# converter.net
KiCad netlist of a schematic drawn in EAGLE
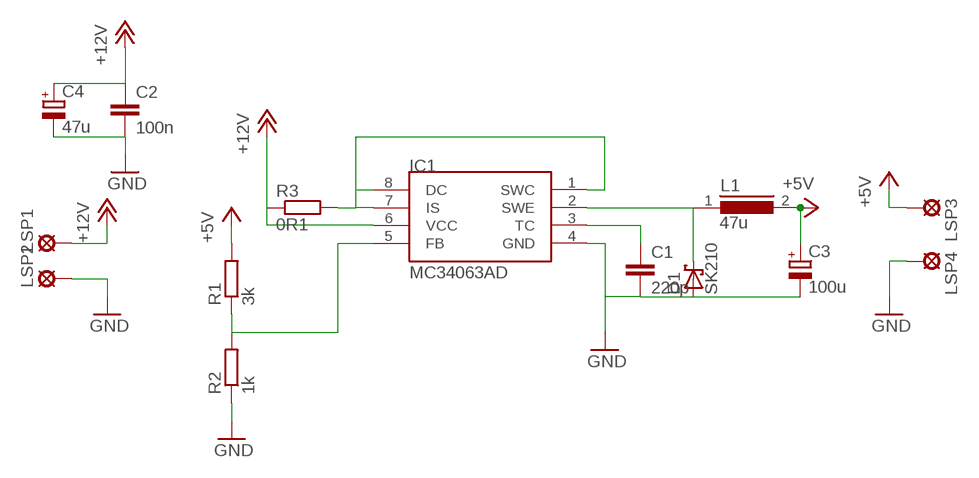
[diagram p0: schematic, sheet 1]

(export (version "E")
  (design (tool "Eeschema 10.0.6"))
  (components
    (comp (ref "C1")
      (value "220p")
      (footprint "eagle-import:C0805")
      (libsource (lib "eagle-import") (part "C-EUC0805"))
    )
    (comp (ref "C2")
      (value "100n")
      (footprint "eagle-import:C0805")
      (libsource (lib "eagle-import") (part "C-EUC0805"))
    )
    (comp (ref "C3")
      (value "100u")
      (footprint "eagle-import:PANASONIC_D")
      (libsource (lib "eagle-import") (part "CPOL-EUD"))
    )
    (comp (ref "C4")
      (value "47u")
      (footprint "eagle-import:PANASONIC_D")
      (libsource (lib "eagle-import") (part "CPOL-EUD"))
    )
    (comp (ref "D1")
      (value "SK210")
      (footprint "eagle-import:SMB")
      (libsource (lib "eagle-import") (part "SCHOTTKY-DIODESMD"))
    )
    (comp (ref "IC1")
      (value "MC34063AD")
      (footprint "eagle-import:SOIC8")
      (libsource (lib "eagle-import") (part "MC34063AD"))
    )
    (comp (ref "L1")
      (value "47u")
      (footprint "eagle-import:DR127")
      (libsource (lib "eagle-import") (part "DR127"))
    )
    (comp (ref "LSP1")
      (value "+12V")
      (footprint "eagle-import:LSP11")
      (libsource (lib "eagle-import") (part "LSP11"))
    )
    (comp (ref "LSP2")
      (value "GND")
      (footprint "eagle-import:LSP11")
      (libsource (lib "eagle-import") (part "LSP11"))
    )
    (comp (ref "LSP3")
      (value "LSP11")
      (footprint "eagle-import:LSP11")
      (libsource (lib "eagle-import") (part "LSP11"))
    )
    (comp (ref "LSP4")
      (value "LSP11")
      (footprint "eagle-import:LSP11")
      (libsource (lib "eagle-import") (part "LSP11"))
    )
    (comp (ref "R1")
      (value "3k")
      (footprint "eagle-import:R0805")
      (libsource (lib "eagle-import") (part "R-EU_R0805"))
    )
    (comp (ref "R2")
      (value "1k")
      (footprint "eagle-import:R0805")
      (libsource (lib "eagle-import") (part "R-EU_R0805"))
    )
    (comp (ref "R3")
      (value "0R1")
      (footprint "eagle-import:R0805")
      (libsource (lib "eagle-import") (part "R-EU_R0805"))
    )
  )
  (nets
    (net (code "1") (name "+5V") (class "Default")
      (node (ref "C3") (pin "+") (pinfunction "+_+") (pintype "passive"))
      (node (ref "L1") (pin "2") (pinfunction "2_2") (pintype "passive"))
      (node (ref "LSP3") (pin "MP") (pinfunction "MP_MP") (pintype "passive"))
      (node (ref "R1") (pin "2") (pinfunction "2_2") (pintype "passive"))
    )
    (net (code "2") (name "+12V") (class "Default")
      (node (ref "C2") (pin "1") (pinfunction "1_1") (pintype "passive"))
      (node (ref "C4") (pin "+") (pinfunction "+_+") (pintype "passive"))
      (node (ref "IC1") (pin "6") (pinfunction "VCC_6") (pintype "passive"))
      (node (ref "LSP1") (pin "MP") (pinfunction "MP_MP") (pintype "passive"))
      (node (ref "R3") (pin "1") (pinfunction "1_1") (pintype "passive"))
    )
    (net (code "3") (name "GND") (class "Default")
      (node (ref "C1") (pin "2") (pinfunction "2_2") (pintype "passive"))
      (node (ref "C2") (pin "2") (pinfunction "2_2") (pintype "passive"))
      (node (ref "C3") (pin "-") (pinfunction "-_-") (pintype "passive"))
      (node (ref "C4") (pin "-") (pinfunction "-_-") (pintype "passive"))
      (node (ref "D1") (pin "A") (pinfunction "A_A") (pintype "passive"))
      (node (ref "IC1") (pin "4") (pinfunction "GND_4") (pintype "passive"))
      (node (ref "LSP2") (pin "MP") (pinfunction "MP_MP") (pintype "passive"))
      (node (ref "LSP4") (pin "MP") (pinfunction "MP_MP") (pintype "passive"))
      (node (ref "R2") (pin "1") (pinfunction "1_1") (pintype "passive"))
    )
    (net (code "4") (name "Net-(IC1-DC)") (class "Default")
      (node (ref "IC1") (pin "1") (pinfunction "SWC_1") (pintype "passive"))
      (node (ref "IC1") (pin "7") (pinfunction "IS_7") (pintype "passive"))
      (node (ref "IC1") (pin "8") (pinfunction "DC_8") (pintype "passive"))
      (node (ref "R3") (pin "2") (pinfunction "2_2") (pintype "passive"))
    )
    (net (code "5") (name "Net-(IC1-FB)") (class "Default")
      (node (ref "IC1") (pin "5") (pinfunction "FB_5") (pintype "passive"))
      (node (ref "R1") (pin "1") (pinfunction "1_1") (pintype "passive"))
      (node (ref "R2") (pin "2") (pinfunction "2_2") (pintype "passive"))
    )
    (net (code "6") (name "Net-(IC1-SWE)") (class "Default")
      (node (ref "D1") (pin "C") (pinfunction "C_C") (pintype "passive"))
      (node (ref "IC1") (pin "2") (pinfunction "SWE_2") (pintype "passive"))
      (node (ref "L1") (pin "1") (pinfunction "1_1") (pintype "passive"))
    )
    (net (code "7") (name "Net-(IC1-TC)") (class "Default")
      (node (ref "C1") (pin "1") (pinfunction "1_1") (pintype "passive"))
      (node (ref "IC1") (pin "3") (pinfunction "TC_3") (pintype "passive"))
    )
  )
)
